# SimulatorT2PowerRevB.net
KiCad netlist of a schematic drawn in EAGLE
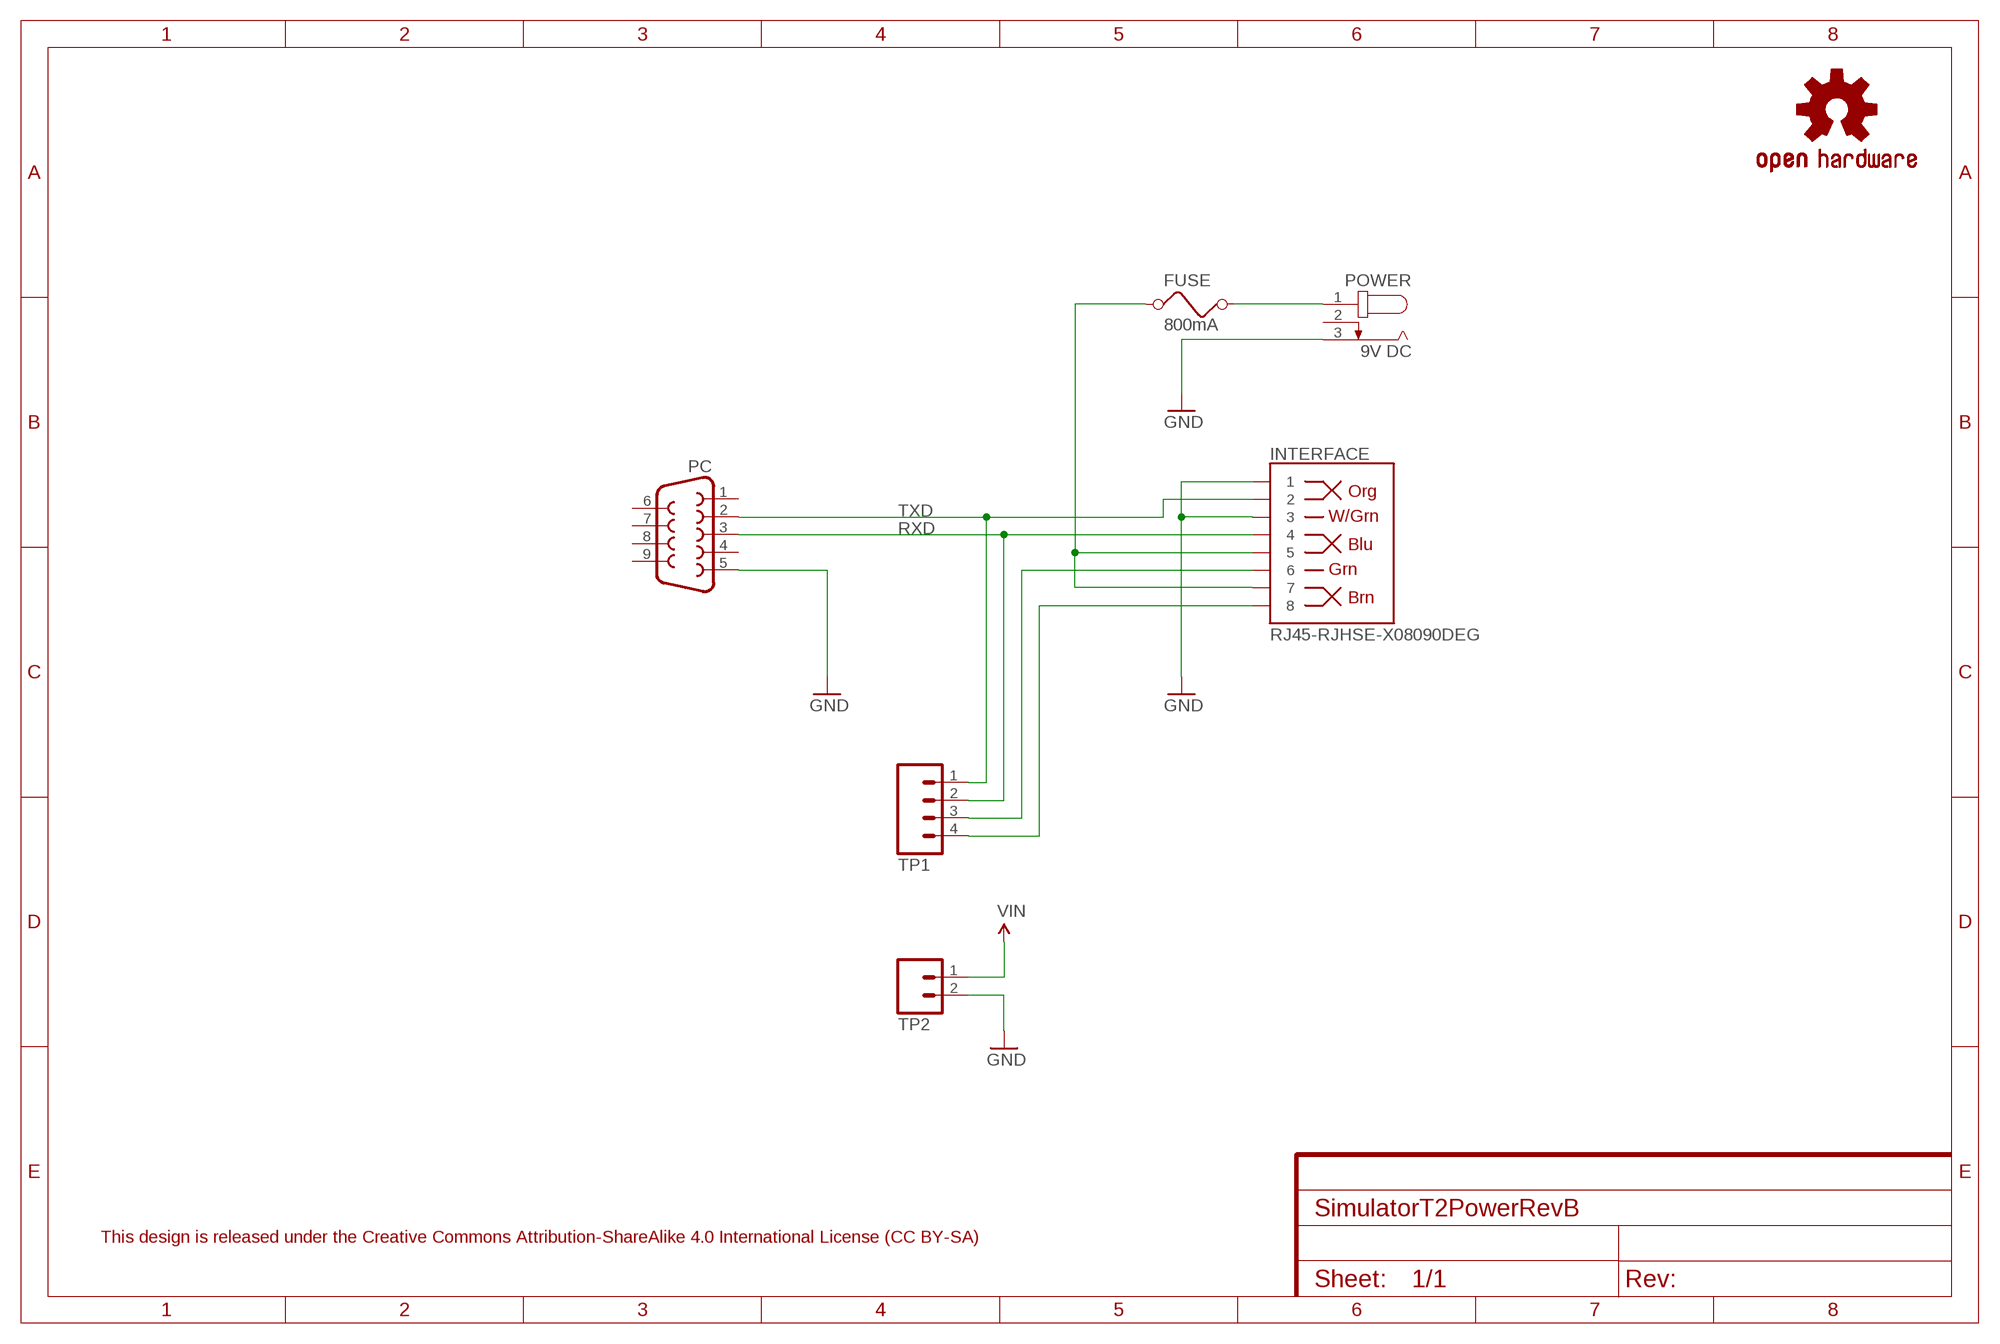
[diagram p0: schematic, sheet 1]

(export (version "E")
  (design (tool "Eeschema 10.0.6"))
  (components
    (comp (ref "FUSE")
      (value "800mA")
      (footprint "eagle-import:MCOMP-FUSE-HOLDER-PCB")
      (libsource (lib "eagle-import") (part "FUSE-HOLDER-PCB"))
    )
    (comp (ref "INTERFACE")
      (value "RJ45-RJHSE-X08090DEG")
      (footprint "eagle-import:RJ45-RJHSE-5080")
      (libsource (lib "eagle-import") (part "RJ45-RJHSE-X08090DEG"))
    )
    (comp (ref "LOGO1")
      (value "OSHW-LOGOS")
      (footprint "eagle-import:OSHW-LOGO-S")
      (libsource (lib "eagle-import") (part "OSHW-LOGOS"))
    )
    (comp (ref "PC")
      (value "DB9-CONNECTOR-PCBFEMALE")
      (footprint "eagle-import:MULTICOMP-DB9-FEMALE-PCB-90DEG")
      (libsource (lib "eagle-import") (part "DB9-CONNECTOR-PCBFEMALE"))
    )
    (comp (ref "POWER")
      (value "9V DC")
      (footprint "eagle-import:CLIFF-FC681465P-DC-JACK")
      (libsource (lib "eagle-import") (part "DC-POWER-JACK-PCB"))
    )
    (comp (ref "TP1")
      (value "M04PTH")
      (footprint "eagle-import:1X04")
      (libsource (lib "eagle-import") (part "M04PTH"))
    )
    (comp (ref "TP2")
      (value "M02PTH")
      (footprint "eagle-import:1X02")
      (libsource (lib "eagle-import") (part "M02PTH"))
    )
  )
  (nets
    (net (code "1") (name "/RXD") (class "Default")
      (node (ref "INTERFACE") (pin "4") (pinfunction "4_4") (pintype "bidirectional"))
      (node (ref "PC") (pin "3") (pinfunction "3_3") (pintype "passive"))
      (node (ref "TP1") (pin "2") (pinfunction "2_2") (pintype "passive"))
    )
    (net (code "2") (name "/TXD") (class "Default")
      (node (ref "INTERFACE") (pin "2") (pinfunction "2_2") (pintype "bidirectional"))
      (node (ref "PC") (pin "2") (pinfunction "2_2") (pintype "passive"))
      (node (ref "TP1") (pin "1") (pinfunction "1_1") (pintype "passive"))
    )
    (net (code "3") (name "GND") (class "Default")
      (node (ref "INTERFACE") (pin "1") (pinfunction "1_1") (pintype "bidirectional"))
      (node (ref "INTERFACE") (pin "3") (pinfunction "3_3") (pintype "bidirectional"))
      (node (ref "PC") (pin "5") (pinfunction "5_5") (pintype "passive"))
      (node (ref "POWER") (pin "3") (pinfunction "3_3") (pintype "passive"))
      (node (ref "TP2") (pin "2") (pinfunction "2_2") (pintype "passive"))
    )
    (net (code "4") (name "Net-(FUSE-Pad1)") (class "Default")
      (node (ref "FUSE") (pin "1") (pinfunction "1_1") (pintype "passive"))
      (node (ref "INTERFACE") (pin "5") (pinfunction "5_5") (pintype "bidirectional"))
      (node (ref "INTERFACE") (pin "7") (pinfunction "7_7") (pintype "bidirectional"))
    )
    (net (code "5") (name "Net-(INTERFACE-Pad6)") (class "Default")
      (node (ref "INTERFACE") (pin "6") (pinfunction "6_6") (pintype "bidirectional"))
      (node (ref "TP1") (pin "3") (pinfunction "3_3") (pintype "passive"))
    )
    (net (code "6") (name "Net-(INTERFACE-Pad8)") (class "Default")
      (node (ref "INTERFACE") (pin "8") (pinfunction "8_8") (pintype "bidirectional"))
      (node (ref "TP1") (pin "4") (pinfunction "4_4") (pintype "passive"))
    )
    (net (code "7") (name "VIN") (class "Default")
      (node (ref "FUSE") (pin "2") (pinfunction "2_2") (pintype "passive"))
      (node (ref "POWER") (pin "1") (pinfunction "1_1") (pintype "passive"))
      (node (ref "TP2") (pin "1") (pinfunction "1_1") (pintype "passive"))
    )
    (net (code "8") (name "unconnected-(PC-Pad1)") (class "Default")
      (node (ref "PC") (pin "1") (pinfunction "1_1") (pintype "passive"))
    )
    (net (code "9") (name "unconnected-(PC-Pad4)") (class "Default")
      (node (ref "PC") (pin "4") (pinfunction "4_4") (pintype "passive"))
    )
    (net (code "10") (name "unconnected-(PC-Pad6)") (class "Default")
      (node (ref "PC") (pin "6") (pinfunction "6_6") (pintype "passive"))
    )
    (net (code "11") (name "unconnected-(PC-Pad7)") (class "Default")
      (node (ref "PC") (pin "7") (pinfunction "7_7") (pintype "passive"))
    )
    (net (code "12") (name "unconnected-(PC-Pad8)") (class "Default")
      (node (ref "PC") (pin "8") (pinfunction "8_8") (pintype "passive"))
    )
    (net (code "13") (name "unconnected-(PC-Pad9)") (class "Default")
      (node (ref "PC") (pin "9") (pinfunction "9_9") (pintype "passive"))
    )
    (net (code "14") (name "unconnected-(POWER-Pad2)") (class "Default")
      (node (ref "POWER") (pin "2") (pinfunction "2_2") (pintype "passive"))
    )
  )
)
